# pressure_and_flow_pcb.net
KiCad netlist of a schematic drawn in EAGLE
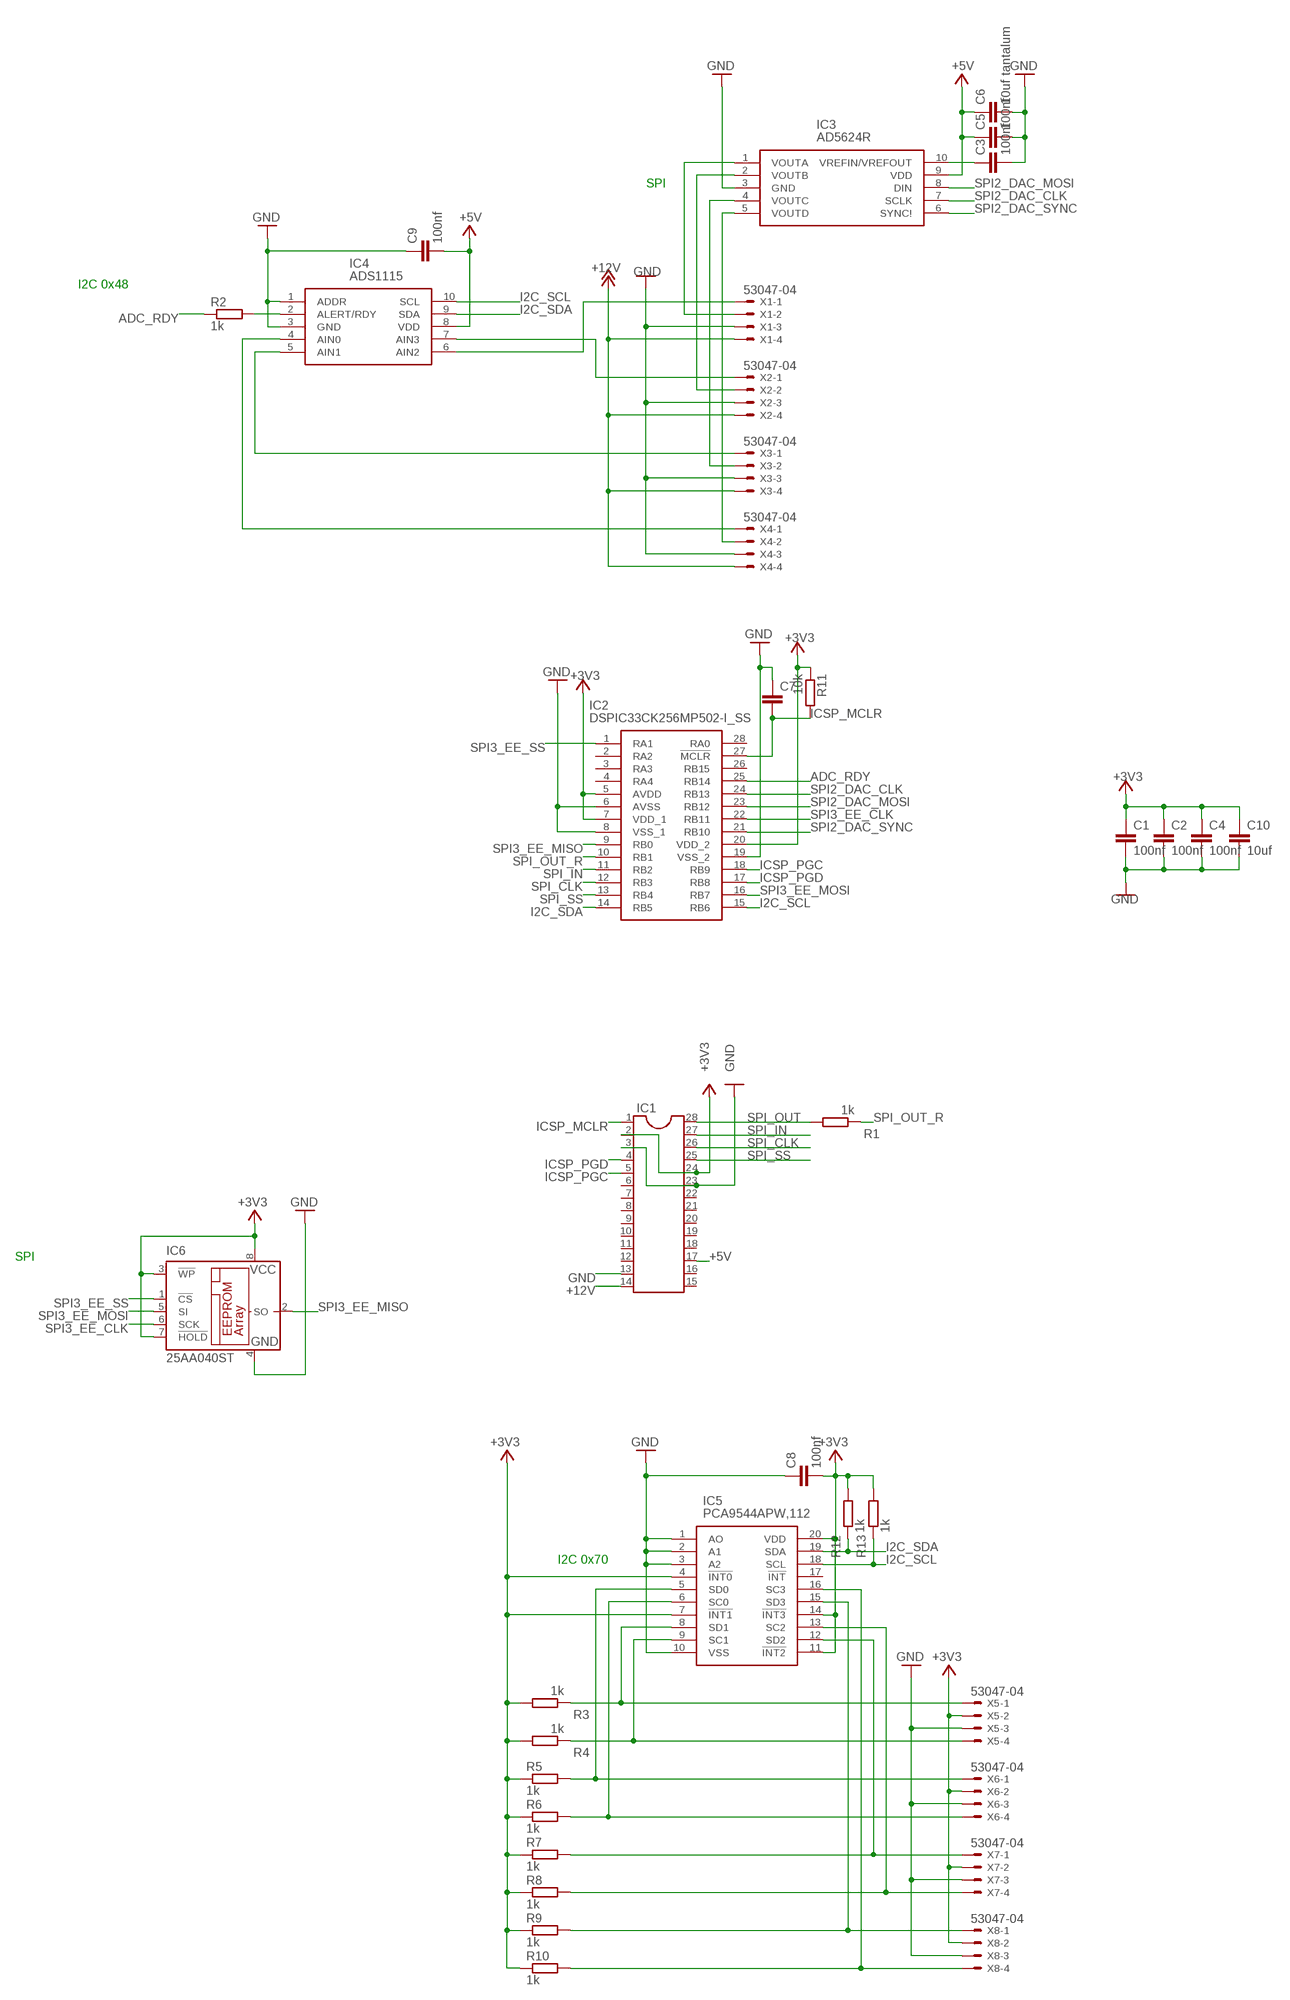
[diagram p0: schematic, sheet 1]

(export (version "E")
  (design (tool "Eeschema 10.0.6"))
  (components
    (comp (ref "C1")
      (value "100nf")
      (footprint "eagle-import:C0603K")
      (libsource (lib "eagle-import") (part "C-EUC0603K"))
    )
    (comp (ref "C2")
      (value "100nf")
      (footprint "eagle-import:C0603K")
      (libsource (lib "eagle-import") (part "C-EUC0603K"))
    )
    (comp (ref "C3")
      (value "100nf")
      (footprint "eagle-import:C0603K")
      (libsource (lib "eagle-import") (part "C-EUC0603K"))
    )
    (comp (ref "C4")
      (value "100nf")
      (footprint "eagle-import:C0603K")
      (libsource (lib "eagle-import") (part "C-EUC0603K"))
    )
    (comp (ref "C5")
      (value "100nf")
      (footprint "eagle-import:C0603K")
      (libsource (lib "eagle-import") (part "C-EUC0603K"))
    )
    (comp (ref "C6")
      (value "10uf tantalum")
      (footprint "eagle-import:C0603K")
      (libsource (lib "eagle-import") (part "C-EUC0603K"))
    )
    (comp (ref "C7")
      (value "C-EUC0603K")
      (footprint "eagle-import:C0603K")
      (libsource (lib "eagle-import") (part "C-EUC0603K"))
    )
    (comp (ref "C8")
      (value "100nf")
      (footprint "eagle-import:C0603K")
      (libsource (lib "eagle-import") (part "C-EUC0603K"))
    )
    (comp (ref "C9")
      (value "100nf")
      (footprint "eagle-import:C0603K")
      (libsource (lib "eagle-import") (part "C-EUC0603K"))
    )
    (comp (ref "C10")
      (value "10uf")
      (footprint "eagle-import:C0603K")
      (libsource (lib "eagle-import") (part "C-EUC0603K"))
    )
    (comp (ref "IC1")
      (value "DIL28")
      (footprint "eagle-import:DIL28-6")
      (libsource (lib "eagle-import") (part "DIL28"))
    )
    (comp (ref "IC2")
      (value "DSPIC33CK256MP502-I_SS")
      (footprint "eagle-import:SOP65P780X200-28N")
      (fields
        (field (name "MANUFACTURER_PART_NUMBER") "dsPIC33CK256MP502-I/SS")
        (field (name "RS_PART_NUMBER") "1793987P")
      )
      (libsource (lib "eagle-import") (part "DSPIC33CK256MP502-I_SS"))
    )
    (comp (ref "IC3")
      (value "AD5624R")
      (footprint "eagle-import:SOP50P490X110-10N")
      (fields
        (field (name "MANUFACTURER_PART_NUMBER") "AD5624RBRMZ-3")
        (field (name "RS_PART_NUMBER") "8065373P")
      )
      (libsource (lib "eagle-import") (part "AD5624RBRMZ-3"))
    )
    (comp (ref "IC4")
      (value "ADS1115")
      (footprint "eagle-import:SOP50P490X110-10N")
      (fields (field (name "MANUFACTURER_PART_NUMBER") "ADS1115BQDGSRQ1"))
      (libsource (lib "eagle-import") (part "ADS1115BQDGSRQ1"))
    )
    (comp (ref "IC5")
      (value "PCA9544APW,112")
      (footprint "eagle-import:SOP65P640X110-20N")
      (fields (field (name "RS_PART_NUMBER") "7258852P"))
      (libsource (lib "eagle-import") (part "PCA9544APW,112"))
    )
    (comp (ref "IC6")
      (value "25AA040ST")
      (footprint "eagle-import:TSSOP8")
      (fields (field (name "MPN") "25AA040A-I/MS"))
      (libsource (lib "eagle-import") (part "25STAA040"))
    )
    (comp (ref "R1")
      (value "1k")
      (footprint "eagle-import:R0603")
      (libsource (lib "eagle-import") (part "R-EU_R0603"))
    )
    (comp (ref "R2")
      (value "1k")
      (footprint "eagle-import:R0603")
      (libsource (lib "eagle-import") (part "R-EU_R0603"))
    )
    (comp (ref "R3")
      (value "1k")
      (footprint "eagle-import:R0603")
      (libsource (lib "eagle-import") (part "R-EU_R0603"))
    )
    (comp (ref "R4")
      (value "1k")
      (footprint "eagle-import:R0603")
      (libsource (lib "eagle-import") (part "R-EU_R0603"))
    )
    (comp (ref "R5")
      (value "1k")
      (footprint "eagle-import:R0603")
      (libsource (lib "eagle-import") (part "R-EU_R0603"))
    )
    (comp (ref "R6")
      (value "1k")
      (footprint "eagle-import:R0603")
      (libsource (lib "eagle-import") (part "R-EU_R0603"))
    )
    (comp (ref "R7")
      (value "1k")
      (footprint "eagle-import:R0603")
      (libsource (lib "eagle-import") (part "R-EU_R0603"))
    )
    (comp (ref "R8")
      (value "1k")
      (footprint "eagle-import:R0603")
      (libsource (lib "eagle-import") (part "R-EU_R0603"))
    )
    (comp (ref "R9")
      (value "1k")
      (footprint "eagle-import:R0603")
      (libsource (lib "eagle-import") (part "R-EU_R0603"))
    )
    (comp (ref "R10")
      (value "1k")
      (footprint "eagle-import:R0603")
      (libsource (lib "eagle-import") (part "R-EU_R0603"))
    )
    (comp (ref "R11")
      (value "10k")
      (footprint "eagle-import:R0603")
      (libsource (lib "eagle-import") (part "R-EU_R0603"))
    )
    (comp (ref "R12")
      (value "1k")
      (footprint "eagle-import:R0603")
      (libsource (lib "eagle-import") (part "R-EU_R0603"))
    )
    (comp (ref "R13")
      (value "1k")
      (footprint "eagle-import:R0603")
      (libsource (lib "eagle-import") (part "R-EU_R0603"))
    )
    (comp (ref "X1")
      (value "53047-04")
      (footprint "eagle-import:53047-04")
      (fields (field (name "MF") "WALDOM/MOLEX") (field (name "MPN") "53047-0410"))
      (libsource (lib "eagle-import") (part "53?-04047"))
    )
    (comp (ref "X2")
      (value "53047-04")
      (footprint "eagle-import:53047-04")
      (fields (field (name "MF") "WALDOM/MOLEX") (field (name "MPN") "53047-0410"))
      (libsource (lib "eagle-import") (part "53?-04047"))
    )
    (comp (ref "X3")
      (value "53047-04")
      (footprint "eagle-import:53047-04")
      (fields (field (name "MF") "WALDOM/MOLEX") (field (name "MPN") "53047-0410"))
      (libsource (lib "eagle-import") (part "53?-04047"))
    )
    (comp (ref "X4")
      (value "53047-04")
      (footprint "eagle-import:53047-04")
      (fields (field (name "MF") "WALDOM/MOLEX") (field (name "MPN") "53047-0410"))
      (libsource (lib "eagle-import") (part "53?-04047"))
    )
    (comp (ref "X5")
      (value "53047-04")
      (footprint "eagle-import:53047-04")
      (fields (field (name "MF") "WALDOM/MOLEX") (field (name "MPN") "53047-0410"))
      (libsource (lib "eagle-import") (part "53?-04047"))
    )
    (comp (ref "X6")
      (value "53047-04")
      (footprint "eagle-import:53047-04")
      (fields (field (name "MF") "WALDOM/MOLEX") (field (name "MPN") "53047-0410"))
      (libsource (lib "eagle-import") (part "53?-04047"))
    )
    (comp (ref "X7")
      (value "53047-04")
      (footprint "eagle-import:53047-04")
      (fields (field (name "MF") "WALDOM/MOLEX") (field (name "MPN") "53047-0410"))
      (libsource (lib "eagle-import") (part "53?-04047"))
    )
    (comp (ref "X8")
      (value "53047-04")
      (footprint "eagle-import:53047-04")
      (fields (field (name "MF") "WALDOM/MOLEX") (field (name "MPN") "53047-0410"))
      (libsource (lib "eagle-import") (part "53?-04047"))
    )
  )
  (nets
    (net (code "1") (name "+3V3") (class "Default")
      (node (ref "C1") (pin "1") (pinfunction "1_1") (pintype "passive"))
      (node (ref "C10") (pin "1") (pinfunction "1_1") (pintype "passive"))
      (node (ref "C2") (pin "1") (pinfunction "1_1") (pintype "passive"))
      (node (ref "C4") (pin "1") (pinfunction "1_1") (pintype "passive"))
      (node (ref "C8") (pin "2") (pinfunction "2_2") (pintype "passive"))
      (node (ref "IC1") (pin "2") (pinfunction "2_2") (pintype "passive"))
      (node (ref "IC1") (pin "24") (pinfunction "24_24") (pintype "passive"))
      (node (ref "IC2") (pin "20") (pinfunction "VDD_2_20") (pintype "bidirectional"))
      (node (ref "IC2") (pin "5") (pinfunction "AVDD_5") (pintype "bidirectional"))
      (node (ref "IC2") (pin "7") (pinfunction "VDD_1_7") (pintype "bidirectional"))
      (node (ref "IC5") (pin "11") (pinfunction "~{INT2}_11") (pintype "bidirectional"))
      (node (ref "IC5") (pin "14") (pinfunction "~{INT3}_14") (pintype "bidirectional"))
      (node (ref "IC5") (pin "20") (pinfunction "VDD_20") (pintype "bidirectional"))
      (node (ref "IC5") (pin "4") (pinfunction "~{INT0}_4") (pintype "bidirectional"))
      (node (ref "IC5") (pin "7") (pinfunction "~{INT1}_7") (pintype "bidirectional"))
      (node (ref "IC6") (pin "3") (pinfunction "~{WP}_3") (pintype "input"))
      (node (ref "IC6") (pin "7") (pinfunction "~{HOLD}_7") (pintype "input"))
      (node (ref "IC6") (pin "8") (pinfunction "VCC_8") (pintype "power_in"))
      (node (ref "R10") (pin "1") (pinfunction "1_1") (pintype "passive"))
      (node (ref "R11") (pin "1") (pinfunction "1_1") (pintype "passive"))
      (node (ref "R12") (pin "2") (pinfunction "2_2") (pintype "passive"))
      (node (ref "R13") (pin "2") (pinfunction "2_2") (pintype "passive"))
      (node (ref "R3") (pin "2") (pinfunction "2_2") (pintype "passive"))
      (node (ref "R4") (pin "2") (pinfunction "2_2") (pintype "passive"))
      (node (ref "R5") (pin "1") (pinfunction "1_1") (pintype "passive"))
      (node (ref "R6") (pin "1") (pinfunction "1_1") (pintype "passive"))
      (node (ref "R7") (pin "1") (pinfunction "1_1") (pintype "passive"))
      (node (ref "R8") (pin "1") (pinfunction "1_1") (pintype "passive"))
      (node (ref "R9") (pin "1") (pinfunction "1_1") (pintype "passive"))
      (node (ref "X5") (pin "2") (pinfunction "S_2") (pintype "passive"))
      (node (ref "X6") (pin "2") (pinfunction "S_2") (pintype "passive"))
      (node (ref "X7") (pin "2") (pinfunction "S_2") (pintype "passive"))
      (node (ref "X8") (pin "2") (pinfunction "S_2") (pintype "passive"))
    )
    (net (code "2") (name "+5V") (class "Default")
      (node (ref "C5") (pin "1") (pinfunction "1_1") (pintype "passive"))
      (node (ref "C6") (pin "1") (pinfunction "1_1") (pintype "passive"))
      (node (ref "C9") (pin "2") (pinfunction "2_2") (pintype "passive"))
      (node (ref "IC1") (pin "17") (pinfunction "17_17") (pintype "passive"))
      (node (ref "IC3") (pin "9") (pinfunction "VDD_9") (pintype "bidirectional"))
      (node (ref "IC4") (pin "8") (pinfunction "VDD_8") (pintype "bidirectional"))
    )
    (net (code "3") (name "+12V") (class "Default")
      (node (ref "IC1") (pin "14") (pinfunction "14_14") (pintype "passive"))
      (node (ref "X1") (pin "4") (pinfunction "S_4") (pintype "passive"))
      (node (ref "X2") (pin "4") (pinfunction "S_4") (pintype "passive"))
      (node (ref "X3") (pin "4") (pinfunction "S_4") (pintype "passive"))
      (node (ref "X4") (pin "4") (pinfunction "S_4") (pintype "passive"))
    )
    (net (code "4") (name "/ADC_RDY") (class "Default")
      (node (ref "IC2") (pin "25") (pinfunction "RB14_25") (pintype "bidirectional"))
      (node (ref "R2") (pin "1") (pinfunction "1_1") (pintype "passive"))
    )
    (net (code "5") (name "/I2C_SCL") (class "Default")
      (node (ref "IC2") (pin "15") (pinfunction "RB6_15") (pintype "bidirectional"))
      (node (ref "IC4") (pin "10") (pinfunction "SCL_10") (pintype "bidirectional"))
      (node (ref "IC5") (pin "18") (pinfunction "SCL_18") (pintype "bidirectional"))
      (node (ref "R13") (pin "1") (pinfunction "1_1") (pintype "passive"))
    )
    (net (code "6") (name "/I2C_SDA") (class "Default")
      (node (ref "IC2") (pin "14") (pinfunction "RB5_14") (pintype "bidirectional"))
      (node (ref "IC4") (pin "9") (pinfunction "SDA_9") (pintype "bidirectional"))
      (node (ref "IC5") (pin "19") (pinfunction "SDA_19") (pintype "bidirectional"))
      (node (ref "R12") (pin "1") (pinfunction "1_1") (pintype "passive"))
    )
    (net (code "7") (name "/ICSP_MCLR") (class "Default")
      (node (ref "C7") (pin "2") (pinfunction "2_2") (pintype "passive"))
      (node (ref "IC1") (pin "1") (pinfunction "1_1") (pintype "passive"))
      (node (ref "IC2") (pin "27") (pinfunction "~{MCLR}_27") (pintype "bidirectional"))
      (node (ref "R11") (pin "2") (pinfunction "2_2") (pintype "passive"))
    )
    (net (code "8") (name "/ICSP_PGC") (class "Default")
      (node (ref "IC1") (pin "5") (pinfunction "5_5") (pintype "passive"))
      (node (ref "IC2") (pin "18") (pinfunction "RB9_18") (pintype "bidirectional"))
    )
    (net (code "9") (name "/ICSP_PGD") (class "Default")
      (node (ref "IC1") (pin "4") (pinfunction "4_4") (pintype "passive"))
      (node (ref "IC2") (pin "17") (pinfunction "RB8_17") (pintype "bidirectional"))
    )
    (net (code "10") (name "/SPI2_DAC_CLK") (class "Default")
      (node (ref "IC2") (pin "24") (pinfunction "RB13_24") (pintype "bidirectional"))
      (node (ref "IC3") (pin "7") (pinfunction "SCLK_7") (pintype "bidirectional"))
    )
    (net (code "11") (name "/SPI2_DAC_MOSI") (class "Default")
      (node (ref "IC2") (pin "23") (pinfunction "RB12_23") (pintype "bidirectional"))
      (node (ref "IC3") (pin "8") (pinfunction "DIN_8") (pintype "bidirectional"))
    )
    (net (code "12") (name "/SPI2_DAC_SYNC") (class "Default")
      (node (ref "IC2") (pin "21") (pinfunction "RB10_21") (pintype "bidirectional"))
      (node (ref "IC3") (pin "6") (pinfunction "SYNC~{}_6") (pintype "bidirectional"))
    )
    (net (code "13") (name "/SPI3_EE_CLK") (class "Default")
      (node (ref "IC2") (pin "22") (pinfunction "RB11_22") (pintype "bidirectional"))
      (node (ref "IC6") (pin "6") (pinfunction "SCK_6") (pintype "input"))
    )
    (net (code "14") (name "/SPI3_EE_MISO") (class "Default")
      (node (ref "IC2") (pin "9") (pinfunction "RB0_9") (pintype "bidirectional"))
      (node (ref "IC6") (pin "2") (pinfunction "SO_2") (pintype "bidirectional"))
    )
    (net (code "15") (name "/SPI3_EE_MOSI") (class "Default")
      (node (ref "IC2") (pin "16") (pinfunction "RB7_16") (pintype "bidirectional"))
      (node (ref "IC6") (pin "5") (pinfunction "SI_5") (pintype "input"))
    )
    (net (code "16") (name "/SPI3_EE_SS") (class "Default")
      (node (ref "IC2") (pin "1") (pinfunction "RA1_1") (pintype "bidirectional"))
      (node (ref "IC6") (pin "1") (pinfunction "~{CS}_1") (pintype "input"))
    )
    (net (code "17") (name "/SPI_CLK") (class "Default")
      (node (ref "IC1") (pin "26") (pinfunction "26_26") (pintype "passive"))
      (node (ref "IC2") (pin "12") (pinfunction "RB3_12") (pintype "bidirectional"))
    )
    (net (code "18") (name "/SPI_IN") (class "Default")
      (node (ref "IC1") (pin "27") (pinfunction "27_27") (pintype "passive"))
      (node (ref "IC2") (pin "11") (pinfunction "RB2_11") (pintype "bidirectional"))
    )
    (net (code "19") (name "/SPI_OUT") (class "Default")
      (node (ref "IC1") (pin "28") (pinfunction "28_28") (pintype "passive"))
      (node (ref "R1") (pin "2") (pinfunction "2_2") (pintype "passive"))
    )
    (net (code "20") (name "/SPI_OUT_R") (class "Default")
      (node (ref "IC2") (pin "10") (pinfunction "RB1_10") (pintype "bidirectional"))
      (node (ref "R1") (pin "1") (pinfunction "1_1") (pintype "passive"))
    )
    (net (code "21") (name "/SPI_SS") (class "Default")
      (node (ref "IC1") (pin "25") (pinfunction "25_25") (pintype "passive"))
      (node (ref "IC2") (pin "13") (pinfunction "RB4_13") (pintype "bidirectional"))
    )
    (net (code "22") (name "GND") (class "Default")
      (node (ref "C1") (pin "2") (pinfunction "2_2") (pintype "passive"))
      (node (ref "C10") (pin "2") (pinfunction "2_2") (pintype "passive"))
      (node (ref "C2") (pin "2") (pinfunction "2_2") (pintype "passive"))
      (node (ref "C3") (pin "2") (pinfunction "2_2") (pintype "passive"))
      (node (ref "C4") (pin "2") (pinfunction "2_2") (pintype "passive"))
      (node (ref "C5") (pin "2") (pinfunction "2_2") (pintype "passive"))
      (node (ref "C6") (pin "2") (pinfunction "2_2") (pintype "passive"))
      (node (ref "C7") (pin "1") (pinfunction "1_1") (pintype "passive"))
      (node (ref "C8") (pin "1") (pinfunction "1_1") (pintype "passive"))
      (node (ref "C9") (pin "1") (pinfunction "1_1") (pintype "passive"))
      (node (ref "IC1") (pin "13") (pinfunction "13_13") (pintype "passive"))
      (node (ref "IC1") (pin "23") (pinfunction "23_23") (pintype "passive"))
      (node (ref "IC1") (pin "3") (pinfunction "3_3") (pintype "passive"))
      (node (ref "IC2") (pin "19") (pinfunction "VSS_2_19") (pintype "bidirectional"))
      (node (ref "IC2") (pin "6") (pinfunction "AVSS_6") (pintype "bidirectional"))
      (node (ref "IC2") (pin "8") (pinfunction "VSS_1_8") (pintype "bidirectional"))
      (node (ref "IC3") (pin "3") (pinfunction "GND_3") (pintype "bidirectional"))
      (node (ref "IC4") (pin "1") (pinfunction "ADDR_1") (pintype "bidirectional"))
      (node (ref "IC4") (pin "3") (pinfunction "GND_3") (pintype "bidirectional"))
      (node (ref "IC5") (pin "1") (pinfunction "AO_1") (pintype "bidirectional"))
      (node (ref "IC5") (pin "10") (pinfunction "VSS_10") (pintype "bidirectional"))
      (node (ref "IC5") (pin "2") (pinfunction "A1_2") (pintype "bidirectional"))
      (node (ref "IC5") (pin "3") (pinfunction "A2_3") (pintype "bidirectional"))
      (node (ref "IC6") (pin "4") (pinfunction "GND_4") (pintype "power_in"))
      (node (ref "X1") (pin "3") (pinfunction "S_3") (pintype "passive"))
      (node (ref "X2") (pin "3") (pinfunction "S_3") (pintype "passive"))
      (node (ref "X3") (pin "3") (pinfunction "S_3") (pintype "passive"))
      (node (ref "X4") (pin "3") (pinfunction "S_3") (pintype "passive"))
      (node (ref "X5") (pin "3") (pinfunction "S_3") (pintype "passive"))
      (node (ref "X6") (pin "3") (pinfunction "S_3") (pintype "passive"))
      (node (ref "X7") (pin "3") (pinfunction "S_3") (pintype "passive"))
      (node (ref "X8") (pin "3") (pinfunction "S_3") (pintype "passive"))
    )
    (net (code "23") (name "Net-(IC3-VOUTA)") (class "Default")
      (node (ref "IC3") (pin "1") (pinfunction "VOUTA_1") (pintype "bidirectional"))
      (node (ref "X1") (pin "2") (pinfunction "S_2") (pintype "passive"))
    )
    (net (code "24") (name "Net-(IC3-VOUTB)") (class "Default")
      (node (ref "IC3") (pin "2") (pinfunction "VOUTB_2") (pintype "bidirectional"))
      (node (ref "X2") (pin "2") (pinfunction "S_2") (pintype "passive"))
    )
    (net (code "25") (name "Net-(IC3-VOUTC)") (class "Default")
      (node (ref "IC3") (pin "4") (pinfunction "VOUTC_4") (pintype "bidirectional"))
      (node (ref "X3") (pin "2") (pinfunction "S_2") (pintype "passive"))
    )
    (net (code "26") (name "Net-(IC3-VOUTD)") (class "Default")
      (node (ref "IC3") (pin "5") (pinfunction "VOUTD_5") (pintype "bidirectional"))
      (node (ref "X4") (pin "2") (pinfunction "S_2") (pintype "passive"))
    )
    (net (code "27") (name "Net-(IC3-VREFIN{slash}VREFOUT)") (class "Default")
      (node (ref "C3") (pin "1") (pinfunction "1_1") (pintype "passive"))
      (node (ref "IC3") (pin "10") (pinfunction "VREFIN/VREFOUT_10") (pintype "bidirectional"))
    )
    (net (code "28") (name "Net-(IC4-AIN0)") (class "Default")
      (node (ref "IC4") (pin "4") (pinfunction "AIN0_4") (pintype "bidirectional"))
      (node (ref "X4") (pin "1") (pinfunction "S_1") (pintype "passive"))
    )
    (net (code "29") (name "Net-(IC4-AIN1)") (class "Default")
      (node (ref "IC4") (pin "5") (pinfunction "AIN1_5") (pintype "bidirectional"))
      (node (ref "X3") (pin "1") (pinfunction "S_1") (pintype "passive"))
    )
    (net (code "30") (name "Net-(IC4-AIN2)") (class "Default")
      (node (ref "IC4") (pin "6") (pinfunction "AIN2_6") (pintype "bidirectional"))
      (node (ref "X1") (pin "1") (pinfunction "S_1") (pintype "passive"))
    )
    (net (code "31") (name "Net-(IC4-AIN3)") (class "Default")
      (node (ref "IC4") (pin "7") (pinfunction "AIN3_7") (pintype "bidirectional"))
      (node (ref "X2") (pin "1") (pinfunction "S_1") (pintype "passive"))
    )
    (net (code "32") (name "Net-(IC4-ALERT{slash}RDY)") (class "Default")
      (node (ref "IC4") (pin "2") (pinfunction "ALERT/RDY_2") (pintype "bidirectional"))
      (node (ref "R2") (pin "2") (pinfunction "2_2") (pintype "passive"))
    )
    (net (code "33") (name "Net-(IC5-SC0)") (class "Default")
      (node (ref "IC5") (pin "6") (pinfunction "SC0_6") (pintype "bidirectional"))
      (node (ref "R6") (pin "2") (pinfunction "2_2") (pintype "passive"))
      (node (ref "X6") (pin "4") (pinfunction "S_4") (pintype "passive"))
    )
    (net (code "34") (name "Net-(IC5-SC1)") (class "Default")
      (node (ref "IC5") (pin "9") (pinfunction "SC1_9") (pintype "bidirectional"))
      (node (ref "R4") (pin "1") (pinfunction "1_1") (pintype "passive"))
      (node (ref "X5") (pin "4") (pinfunction "S_4") (pintype "passive"))
    )
    (net (code "35") (name "Net-(IC5-SC2)") (class "Default")
      (node (ref "IC5") (pin "13") (pinfunction "SC2_13") (pintype "bidirectional"))
      (node (ref "R8") (pin "2") (pinfunction "2_2") (pintype "passive"))
      (node (ref "X7") (pin "4") (pinfunction "S_4") (pintype "passive"))
    )
    (net (code "36") (name "Net-(IC5-SC3)") (class "Default")
      (node (ref "IC5") (pin "16") (pinfunction "SC3_16") (pintype "bidirectional"))
      (node (ref "R10") (pin "2") (pinfunction "2_2") (pintype "passive"))
      (node (ref "X8") (pin "4") (pinfunction "S_4") (pintype "passive"))
    )
    (net (code "37") (name "Net-(IC5-SD0)") (class "Default")
      (node (ref "IC5") (pin "5") (pinfunction "SD0_5") (pintype "bidirectional"))
      (node (ref "R5") (pin "2") (pinfunction "2_2") (pintype "passive"))
      (node (ref "X6") (pin "1") (pinfunction "S_1") (pintype "passive"))
    )
    (net (code "38") (name "Net-(IC5-SD1)") (class "Default")
      (node (ref "IC5") (pin "8") (pinfunction "SD1_8") (pintype "bidirectional"))
      (node (ref "R3") (pin "1") (pinfunction "1_1") (pintype "passive"))
      (node (ref "X5") (pin "1") (pinfunction "S_1") (pintype "passive"))
    )
    (net (code "39") (name "Net-(IC5-SD2)") (class "Default")
      (node (ref "IC5") (pin "12") (pinfunction "SD2_12") (pintype "bidirectional"))
      (node (ref "R7") (pin "2") (pinfunction "2_2") (pintype "passive"))
      (node (ref "X7") (pin "1") (pinfunction "S_1") (pintype "passive"))
    )
    (net (code "40") (name "Net-(IC5-SD3)") (class "Default")
      (node (ref "IC5") (pin "15") (pinfunction "SD3_15") (pintype "bidirectional"))
      (node (ref "R9") (pin "2") (pinfunction "2_2") (pintype "passive"))
      (node (ref "X8") (pin "1") (pinfunction "S_1") (pintype "passive"))
    )
    (net (code "41") (name "unconnected-(IC1-Pad6)") (class "Default")
      (node (ref "IC1") (pin "6") (pinfunction "6_6") (pintype "passive"))
    )
    (net (code "42") (name "unconnected-(IC1-Pad7)") (class "Default")
      (node (ref "IC1") (pin "7") (pinfunction "7_7") (pintype "passive"))
    )
    (net (code "43") (name "unconnected-(IC1-Pad8)") (class "Default")
      (node (ref "IC1") (pin "8") (pinfunction "8_8") (pintype "passive"))
    )
    (net (code "44") (name "unconnected-(IC1-Pad9)") (class "Default")
      (node (ref "IC1") (pin "9") (pinfunction "9_9") (pintype "passive"))
    )
    (net (code "45") (name "unconnected-(IC1-Pad10)") (class "Default")
      (node (ref "IC1") (pin "10") (pinfunction "10_10") (pintype "passive"))
    )
    (net (code "46") (name "unconnected-(IC1-Pad11)") (class "Default")
      (node (ref "IC1") (pin "11") (pinfunction "11_11") (pintype "passive"))
    )
    (net (code "47") (name "unconnected-(IC1-Pad12)") (class "Default")
      (node (ref "IC1") (pin "12") (pinfunction "12_12") (pintype "passive"))
    )
    (net (code "48") (name "unconnected-(IC1-Pad15)") (class "Default")
      (node (ref "IC1") (pin "15") (pinfunction "15_15") (pintype "passive"))
    )
    (net (code "49") (name "unconnected-(IC1-Pad16)") (class "Default")
      (node (ref "IC1") (pin "16") (pinfunction "16_16") (pintype "passive"))
    )
    (net (code "50") (name "unconnected-(IC1-Pad18)") (class "Default")
      (node (ref "IC1") (pin "18") (pinfunction "18_18") (pintype "passive"))
    )
    (net (code "51") (name "unconnected-(IC1-Pad19)") (class "Default")
      (node (ref "IC1") (pin "19") (pinfunction "19_19") (pintype "passive"))
    )
    (net (code "52") (name "unconnected-(IC1-Pad20)") (class "Default")
      (node (ref "IC1") (pin "20") (pinfunction "20_20") (pintype "passive"))
    )
    (net (code "53") (name "unconnected-(IC1-Pad21)") (class "Default")
      (node (ref "IC1") (pin "21") (pinfunction "21_21") (pintype "passive"))
    )
    (net (code "54") (name "unconnected-(IC1-Pad22)") (class "Default")
      (node (ref "IC1") (pin "22") (pinfunction "22_22") (pintype "passive"))
    )
    (net (code "55") (name "unconnected-(IC2-RA0-Pad28)") (class "Default")
      (node (ref "IC2") (pin "28") (pinfunction "RA0_28") (pintype "bidirectional"))
    )
    (net (code "56") (name "unconnected-(IC2-RA2-Pad2)") (class "Default")
      (node (ref "IC2") (pin "2") (pinfunction "RA2_2") (pintype "bidirectional"))
    )
    (net (code "57") (name "unconnected-(IC2-RA3-Pad3)") (class "Default")
      (node (ref "IC2") (pin "3") (pinfunction "RA3_3") (pintype "bidirectional"))
    )
    (net (code "58") (name "unconnected-(IC2-RA4-Pad4)") (class "Default")
      (node (ref "IC2") (pin "4") (pinfunction "RA4_4") (pintype "bidirectional"))
    )
    (net (code "59") (name "unconnected-(IC2-RB15-Pad26)") (class "Default")
      (node (ref "IC2") (pin "26") (pinfunction "RB15_26") (pintype "bidirectional"))
    )
    (net (code "60") (name "unconnected-(IC5-~{INT}-Pad17)") (class "Default")
      (node (ref "IC5") (pin "17") (pinfunction "~{INT}_17") (pintype "bidirectional"))
    )
  )
)
